# Gomez_DMF_v1.net
KiCad netlist of a schematic drawn in EAGLE
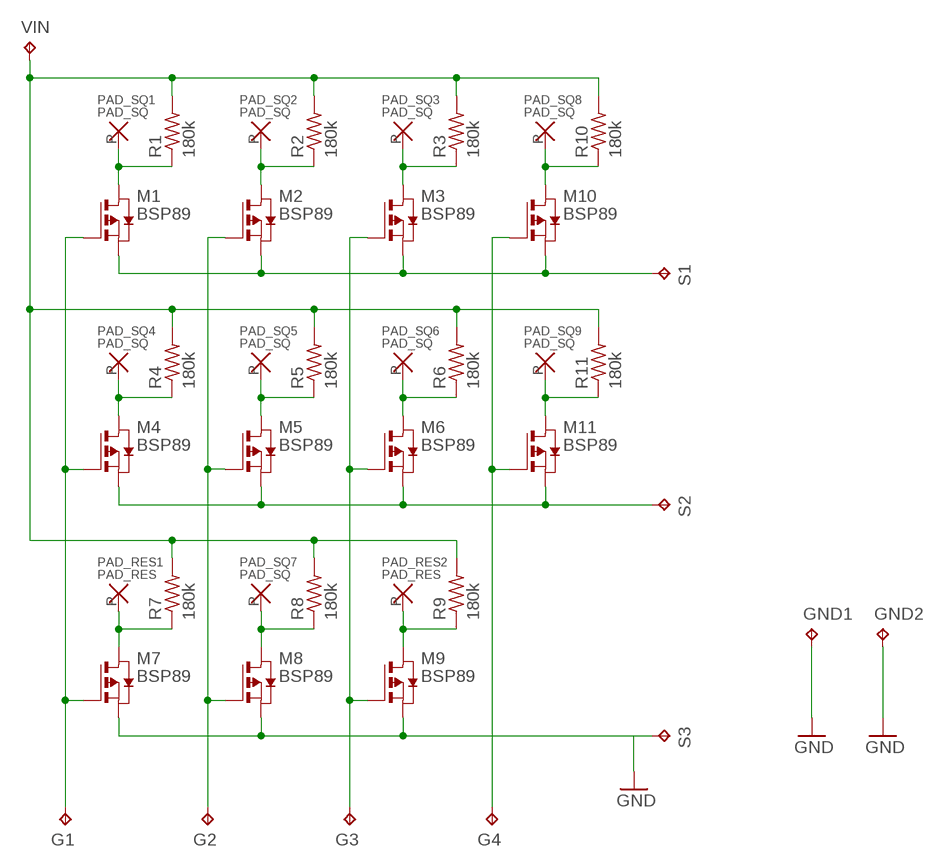
[diagram p0: schematic, sheet 1]

(export (version "E")
  (design (tool "Eeschema 10.0.6"))
  (components
    (comp (ref "G1")
      (value "TPB2,54")
      (footprint "eagle-import:B2,54")
      (libsource (lib "eagle-import") (part "TPB2,54"))
    )
    (comp (ref "G2")
      (value "TPB2,54")
      (footprint "eagle-import:B2,54")
      (libsource (lib "eagle-import") (part "TPB2,54"))
    )
    (comp (ref "G3")
      (value "TPB2,54")
      (footprint "eagle-import:B2,54")
      (libsource (lib "eagle-import") (part "TPB2,54"))
    )
    (comp (ref "G4")
      (value "TPB2,54")
      (footprint "eagle-import:B2,54")
      (libsource (lib "eagle-import") (part "TPB2,54"))
    )
    (comp (ref "GND1")
      (value "TPB2,54")
      (footprint "eagle-import:B2,54")
      (libsource (lib "eagle-import") (part "TPB2,54"))
    )
    (comp (ref "GND2")
      (value "TPB2,54")
      (footprint "eagle-import:B2,54")
      (libsource (lib "eagle-import") (part "TPB2,54"))
    )
    (comp (ref "M1")
      (value "BSP89")
      (footprint "eagle-import:SOT223")
      (libsource (lib "eagle-import") (part "PMOSSOT223"))
    )
    (comp (ref "M2")
      (value "BSP89")
      (footprint "eagle-import:SOT223")
      (libsource (lib "eagle-import") (part "PMOSSOT223"))
    )
    (comp (ref "M3")
      (value "BSP89")
      (footprint "eagle-import:SOT223")
      (libsource (lib "eagle-import") (part "PMOSSOT223"))
    )
    (comp (ref "M4")
      (value "BSP89")
      (footprint "eagle-import:SOT223")
      (libsource (lib "eagle-import") (part "PMOSSOT223"))
    )
    (comp (ref "M5")
      (value "BSP89")
      (footprint "eagle-import:SOT223")
      (libsource (lib "eagle-import") (part "PMOSSOT223"))
    )
    (comp (ref "M6")
      (value "BSP89")
      (footprint "eagle-import:SOT223")
      (libsource (lib "eagle-import") (part "PMOSSOT223"))
    )
    (comp (ref "M7")
      (value "BSP89")
      (footprint "eagle-import:SOT223")
      (libsource (lib "eagle-import") (part "PMOSSOT223"))
    )
    (comp (ref "M8")
      (value "BSP89")
      (footprint "eagle-import:SOT223")
      (libsource (lib "eagle-import") (part "PMOSSOT223"))
    )
    (comp (ref "M9")
      (value "BSP89")
      (footprint "eagle-import:SOT223")
      (libsource (lib "eagle-import") (part "PMOSSOT223"))
    )
    (comp (ref "M10")
      (value "BSP89")
      (footprint "eagle-import:SOT223")
      (libsource (lib "eagle-import") (part "PMOSSOT223"))
    )
    (comp (ref "M11")
      (value "BSP89")
      (footprint "eagle-import:SOT223")
      (libsource (lib "eagle-import") (part "PMOSSOT223"))
    )
    (comp (ref "PAD_RES1")
      (value "PAD_RES")
      (footprint "eagle-import:PAD_RES")
      (libsource (lib "eagle-import") (part "PAD_RES"))
    )
    (comp (ref "PAD_RES2")
      (value "PAD_RES")
      (footprint "eagle-import:PAD_RES")
      (libsource (lib "eagle-import") (part "PAD_RES"))
    )
    (comp (ref "PAD_SQ1")
      (value "PAD_SQ")
      (footprint "eagle-import:PAD_SQ")
      (libsource (lib "eagle-import") (part "PAD_SQ"))
    )
    (comp (ref "PAD_SQ2")
      (value "PAD_SQ")
      (footprint "eagle-import:PAD_SQ")
      (libsource (lib "eagle-import") (part "PAD_SQ"))
    )
    (comp (ref "PAD_SQ3")
      (value "PAD_SQ")
      (footprint "eagle-import:PAD_SQ")
      (libsource (lib "eagle-import") (part "PAD_SQ"))
    )
    (comp (ref "PAD_SQ4")
      (value "PAD_SQ")
      (footprint "eagle-import:PAD_SQ")
      (libsource (lib "eagle-import") (part "PAD_SQ"))
    )
    (comp (ref "PAD_SQ5")
      (value "PAD_SQ")
      (footprint "eagle-import:PAD_SQ")
      (libsource (lib "eagle-import") (part "PAD_SQ"))
    )
    (comp (ref "PAD_SQ6")
      (value "PAD_SQ")
      (footprint "eagle-import:PAD_SQ")
      (libsource (lib "eagle-import") (part "PAD_SQ"))
    )
    (comp (ref "PAD_SQ7")
      (value "PAD_SQ")
      (footprint "eagle-import:PAD_SQ")
      (libsource (lib "eagle-import") (part "PAD_SQ"))
    )
    (comp (ref "PAD_SQ8")
      (value "PAD_SQ")
      (footprint "eagle-import:PAD_SQ")
      (libsource (lib "eagle-import") (part "PAD_SQ"))
    )
    (comp (ref "PAD_SQ9")
      (value "PAD_SQ")
      (footprint "eagle-import:PAD_SQ")
      (libsource (lib "eagle-import") (part "PAD_SQ"))
    )
    (comp (ref "R1")
      (value "180k")
      (footprint "eagle-import:V234_12")
      (libsource (lib "eagle-import") (part "R-US_V234/12"))
    )
    (comp (ref "R2")
      (value "180k")
      (footprint "eagle-import:V234_12")
      (libsource (lib "eagle-import") (part "R-US_V234/12"))
    )
    (comp (ref "R3")
      (value "180k")
      (footprint "eagle-import:V234_12")
      (libsource (lib "eagle-import") (part "R-US_V234/12"))
    )
    (comp (ref "R4")
      (value "180k")
      (footprint "eagle-import:V234_12")
      (libsource (lib "eagle-import") (part "R-US_V234/12"))
    )
    (comp (ref "R5")
      (value "180k")
      (footprint "eagle-import:V234_12")
      (libsource (lib "eagle-import") (part "R-US_V234/12"))
    )
    (comp (ref "R6")
      (value "180k")
      (footprint "eagle-import:V234_12")
      (libsource (lib "eagle-import") (part "R-US_V234/12"))
    )
    (comp (ref "R7")
      (value "180k")
      (footprint "eagle-import:V234_12")
      (libsource (lib "eagle-import") (part "R-US_V234/12"))
    )
    (comp (ref "R8")
      (value "180k")
      (footprint "eagle-import:V234_12")
      (libsource (lib "eagle-import") (part "R-US_V234/12"))
    )
    (comp (ref "R9")
      (value "180k")
      (footprint "eagle-import:V234_12")
      (libsource (lib "eagle-import") (part "R-US_V234/12"))
    )
    (comp (ref "R10")
      (value "180k")
      (footprint "eagle-import:V234_12")
      (libsource (lib "eagle-import") (part "R-US_V234/12"))
    )
    (comp (ref "R11")
      (value "180k")
      (footprint "eagle-import:V234_12")
      (libsource (lib "eagle-import") (part "R-US_V234/12"))
    )
    (comp (ref "S1")
      (value "TPB2,54")
      (footprint "eagle-import:B2,54")
      (libsource (lib "eagle-import") (part "TPB2,54"))
    )
    (comp (ref "S2")
      (value "TPB2,54")
      (footprint "eagle-import:B2,54")
      (libsource (lib "eagle-import") (part "TPB2,54"))
    )
    (comp (ref "S3")
      (value "TPB2,54")
      (footprint "eagle-import:B2,54")
      (libsource (lib "eagle-import") (part "TPB2,54"))
    )
    (comp (ref "VIN")
      (value "TPB2,54")
      (footprint "eagle-import:B2,54")
      (libsource (lib "eagle-import") (part "TPB2,54"))
    )
  )
  (nets
    (net (code "1") (name "GND") (class "Default")
      (node (ref "GND1") (pin "TP") (pinfunction "TP_TP") (pintype "input"))
      (node (ref "GND2") (pin "TP") (pinfunction "TP_TP") (pintype "input"))
    )
    (net (code "2") (name "Net-(M1-G)") (class "Default")
      (node (ref "G1") (pin "TP") (pinfunction "TP_TP") (pintype "input"))
      (node (ref "M1") (pin "1") (pinfunction "G_1") (pintype "passive"))
      (node (ref "M4") (pin "1") (pinfunction "G_1") (pintype "passive"))
      (node (ref "M7") (pin "1") (pinfunction "G_1") (pintype "passive"))
    )
    (net (code "3") (name "Net-(M1-S)") (class "Default")
      (node (ref "M1") (pin "3") (pinfunction "S_3") (pintype "passive"))
      (node (ref "M10") (pin "3") (pinfunction "S_3") (pintype "passive"))
      (node (ref "M2") (pin "3") (pinfunction "S_3") (pintype "passive"))
      (node (ref "M3") (pin "3") (pinfunction "S_3") (pintype "passive"))
      (node (ref "S1") (pin "TP") (pinfunction "TP_TP") (pintype "input"))
    )
    (net (code "4") (name "Net-(M2-G)") (class "Default")
      (node (ref "G2") (pin "TP") (pinfunction "TP_TP") (pintype "input"))
      (node (ref "M2") (pin "1") (pinfunction "G_1") (pintype "passive"))
      (node (ref "M5") (pin "1") (pinfunction "G_1") (pintype "passive"))
      (node (ref "M8") (pin "1") (pinfunction "G_1") (pintype "passive"))
    )
    (net (code "5") (name "Net-(M3-G)") (class "Default")
      (node (ref "G3") (pin "TP") (pinfunction "TP_TP") (pintype "input"))
      (node (ref "M3") (pin "1") (pinfunction "G_1") (pintype "passive"))
      (node (ref "M6") (pin "1") (pinfunction "G_1") (pintype "passive"))
      (node (ref "M9") (pin "1") (pinfunction "G_1") (pintype "passive"))
    )
    (net (code "6") (name "Net-(M7-S)") (class "Default")
      (node (ref "M7") (pin "3") (pinfunction "S_3") (pintype "passive"))
      (node (ref "M8") (pin "3") (pinfunction "S_3") (pintype "passive"))
      (node (ref "M9") (pin "3") (pinfunction "S_3") (pintype "passive"))
      (node (ref "S3") (pin "TP") (pinfunction "TP_TP") (pintype "input"))
    )
    (net (code "7") (name "Net-(M10-G)") (class "Default")
      (node (ref "G4") (pin "TP") (pinfunction "TP_TP") (pintype "input"))
      (node (ref "M10") (pin "1") (pinfunction "G_1") (pintype "passive"))
      (node (ref "M11") (pin "1") (pinfunction "G_1") (pintype "passive"))
    )
    (net (code "8") (name "Net-(M11-S)") (class "Default")
      (node (ref "M11") (pin "3") (pinfunction "S_3") (pintype "passive"))
      (node (ref "M4") (pin "3") (pinfunction "S_3") (pintype "passive"))
      (node (ref "M5") (pin "3") (pinfunction "S_3") (pintype "passive"))
      (node (ref "M6") (pin "3") (pinfunction "S_3") (pintype "passive"))
      (node (ref "S2") (pin "TP") (pinfunction "TP_TP") (pintype "input"))
    )
    (net (code "9") (name "Net-(PAD_RES1-1)") (class "Default")
      (node (ref "M7") (pin "2") (pinfunction "D_2") (pintype "passive"))
      (node (ref "M7") (pin "4") (pinfunction "D_4") (pintype "passive"))
      (node (ref "PAD_RES1") (pin "P") (pinfunction "1_P") (pintype "input"))
      (node (ref "R7") (pin "1") (pinfunction "1_1") (pintype "passive"))
    )
    (net (code "10") (name "Net-(PAD_RES2-1)") (class "Default")
      (node (ref "M9") (pin "2") (pinfunction "D_2") (pintype "passive"))
      (node (ref "M9") (pin "4") (pinfunction "D_4") (pintype "passive"))
      (node (ref "PAD_RES2") (pin "P") (pinfunction "1_P") (pintype "input"))
      (node (ref "R9") (pin "1") (pinfunction "1_1") (pintype "passive"))
    )
    (net (code "11") (name "Net-(PAD_SQ1-1)") (class "Default")
      (node (ref "M1") (pin "2") (pinfunction "D_2") (pintype "passive"))
      (node (ref "M1") (pin "4") (pinfunction "D_4") (pintype "passive"))
      (node (ref "PAD_SQ1") (pin "P") (pinfunction "1_P") (pintype "input"))
      (node (ref "R1") (pin "1") (pinfunction "1_1") (pintype "passive"))
    )
    (net (code "12") (name "Net-(PAD_SQ2-1)") (class "Default")
      (node (ref "M2") (pin "2") (pinfunction "D_2") (pintype "passive"))
      (node (ref "M2") (pin "4") (pinfunction "D_4") (pintype "passive"))
      (node (ref "PAD_SQ2") (pin "P") (pinfunction "1_P") (pintype "input"))
      (node (ref "R2") (pin "1") (pinfunction "1_1") (pintype "passive"))
    )
    (net (code "13") (name "Net-(PAD_SQ3-1)") (class "Default")
      (node (ref "M3") (pin "2") (pinfunction "D_2") (pintype "passive"))
      (node (ref "M3") (pin "4") (pinfunction "D_4") (pintype "passive"))
      (node (ref "PAD_SQ3") (pin "P") (pinfunction "1_P") (pintype "input"))
      (node (ref "R3") (pin "1") (pinfunction "1_1") (pintype "passive"))
    )
    (net (code "14") (name "Net-(PAD_SQ4-1)") (class "Default")
      (node (ref "M4") (pin "2") (pinfunction "D_2") (pintype "passive"))
      (node (ref "M4") (pin "4") (pinfunction "D_4") (pintype "passive"))
      (node (ref "PAD_SQ4") (pin "P") (pinfunction "1_P") (pintype "input"))
      (node (ref "R4") (pin "1") (pinfunction "1_1") (pintype "passive"))
    )
    (net (code "15") (name "Net-(PAD_SQ5-1)") (class "Default")
      (node (ref "M5") (pin "2") (pinfunction "D_2") (pintype "passive"))
      (node (ref "M5") (pin "4") (pinfunction "D_4") (pintype "passive"))
      (node (ref "PAD_SQ5") (pin "P") (pinfunction "1_P") (pintype "input"))
      (node (ref "R5") (pin "1") (pinfunction "1_1") (pintype "passive"))
    )
    (net (code "16") (name "Net-(PAD_SQ6-1)") (class "Default")
      (node (ref "M6") (pin "2") (pinfunction "D_2") (pintype "passive"))
      (node (ref "M6") (pin "4") (pinfunction "D_4") (pintype "passive"))
      (node (ref "PAD_SQ6") (pin "P") (pinfunction "1_P") (pintype "input"))
      (node (ref "R6") (pin "1") (pinfunction "1_1") (pintype "passive"))
    )
    (net (code "17") (name "Net-(PAD_SQ7-1)") (class "Default")
      (node (ref "M8") (pin "2") (pinfunction "D_2") (pintype "passive"))
      (node (ref "M8") (pin "4") (pinfunction "D_4") (pintype "passive"))
      (node (ref "PAD_SQ7") (pin "P") (pinfunction "1_P") (pintype "input"))
      (node (ref "R8") (pin "1") (pinfunction "1_1") (pintype "passive"))
    )
    (net (code "18") (name "Net-(PAD_SQ8-1)") (class "Default")
      (node (ref "M10") (pin "2") (pinfunction "D_2") (pintype "passive"))
      (node (ref "M10") (pin "4") (pinfunction "D_4") (pintype "passive"))
      (node (ref "PAD_SQ8") (pin "P") (pinfunction "1_P") (pintype "input"))
      (node (ref "R10") (pin "1") (pinfunction "1_1") (pintype "passive"))
    )
    (net (code "19") (name "Net-(PAD_SQ9-1)") (class "Default")
      (node (ref "M11") (pin "2") (pinfunction "D_2") (pintype "passive"))
      (node (ref "M11") (pin "4") (pinfunction "D_4") (pintype "passive"))
      (node (ref "PAD_SQ9") (pin "P") (pinfunction "1_P") (pintype "input"))
      (node (ref "R11") (pin "1") (pinfunction "1_1") (pintype "passive"))
    )
    (net (code "20") (name "Net-(R1-Pad2)") (class "Default")
      (node (ref "R1") (pin "2") (pinfunction "2_2") (pintype "passive"))
      (node (ref "R10") (pin "2") (pinfunction "2_2") (pintype "passive"))
      (node (ref "R11") (pin "2") (pinfunction "2_2") (pintype "passive"))
      (node (ref "R2") (pin "2") (pinfunction "2_2") (pintype "passive"))
      (node (ref "R3") (pin "2") (pinfunction "2_2") (pintype "passive"))
      (node (ref "R4") (pin "2") (pinfunction "2_2") (pintype "passive"))
      (node (ref "R5") (pin "2") (pinfunction "2_2") (pintype "passive"))
      (node (ref "R6") (pin "2") (pinfunction "2_2") (pintype "passive"))
      (node (ref "R7") (pin "2") (pinfunction "2_2") (pintype "passive"))
      (node (ref "R8") (pin "2") (pinfunction "2_2") (pintype "passive"))
      (node (ref "R9") (pin "2") (pinfunction "2_2") (pintype "passive"))
      (node (ref "VIN") (pin "TP") (pinfunction "TP_TP") (pintype "input"))
    )
  )
)
